# SCH_Cocktail-Hat-Solder-Terminals_2026-0.net
KiCad netlist of a schematic drawn in EasyEDA
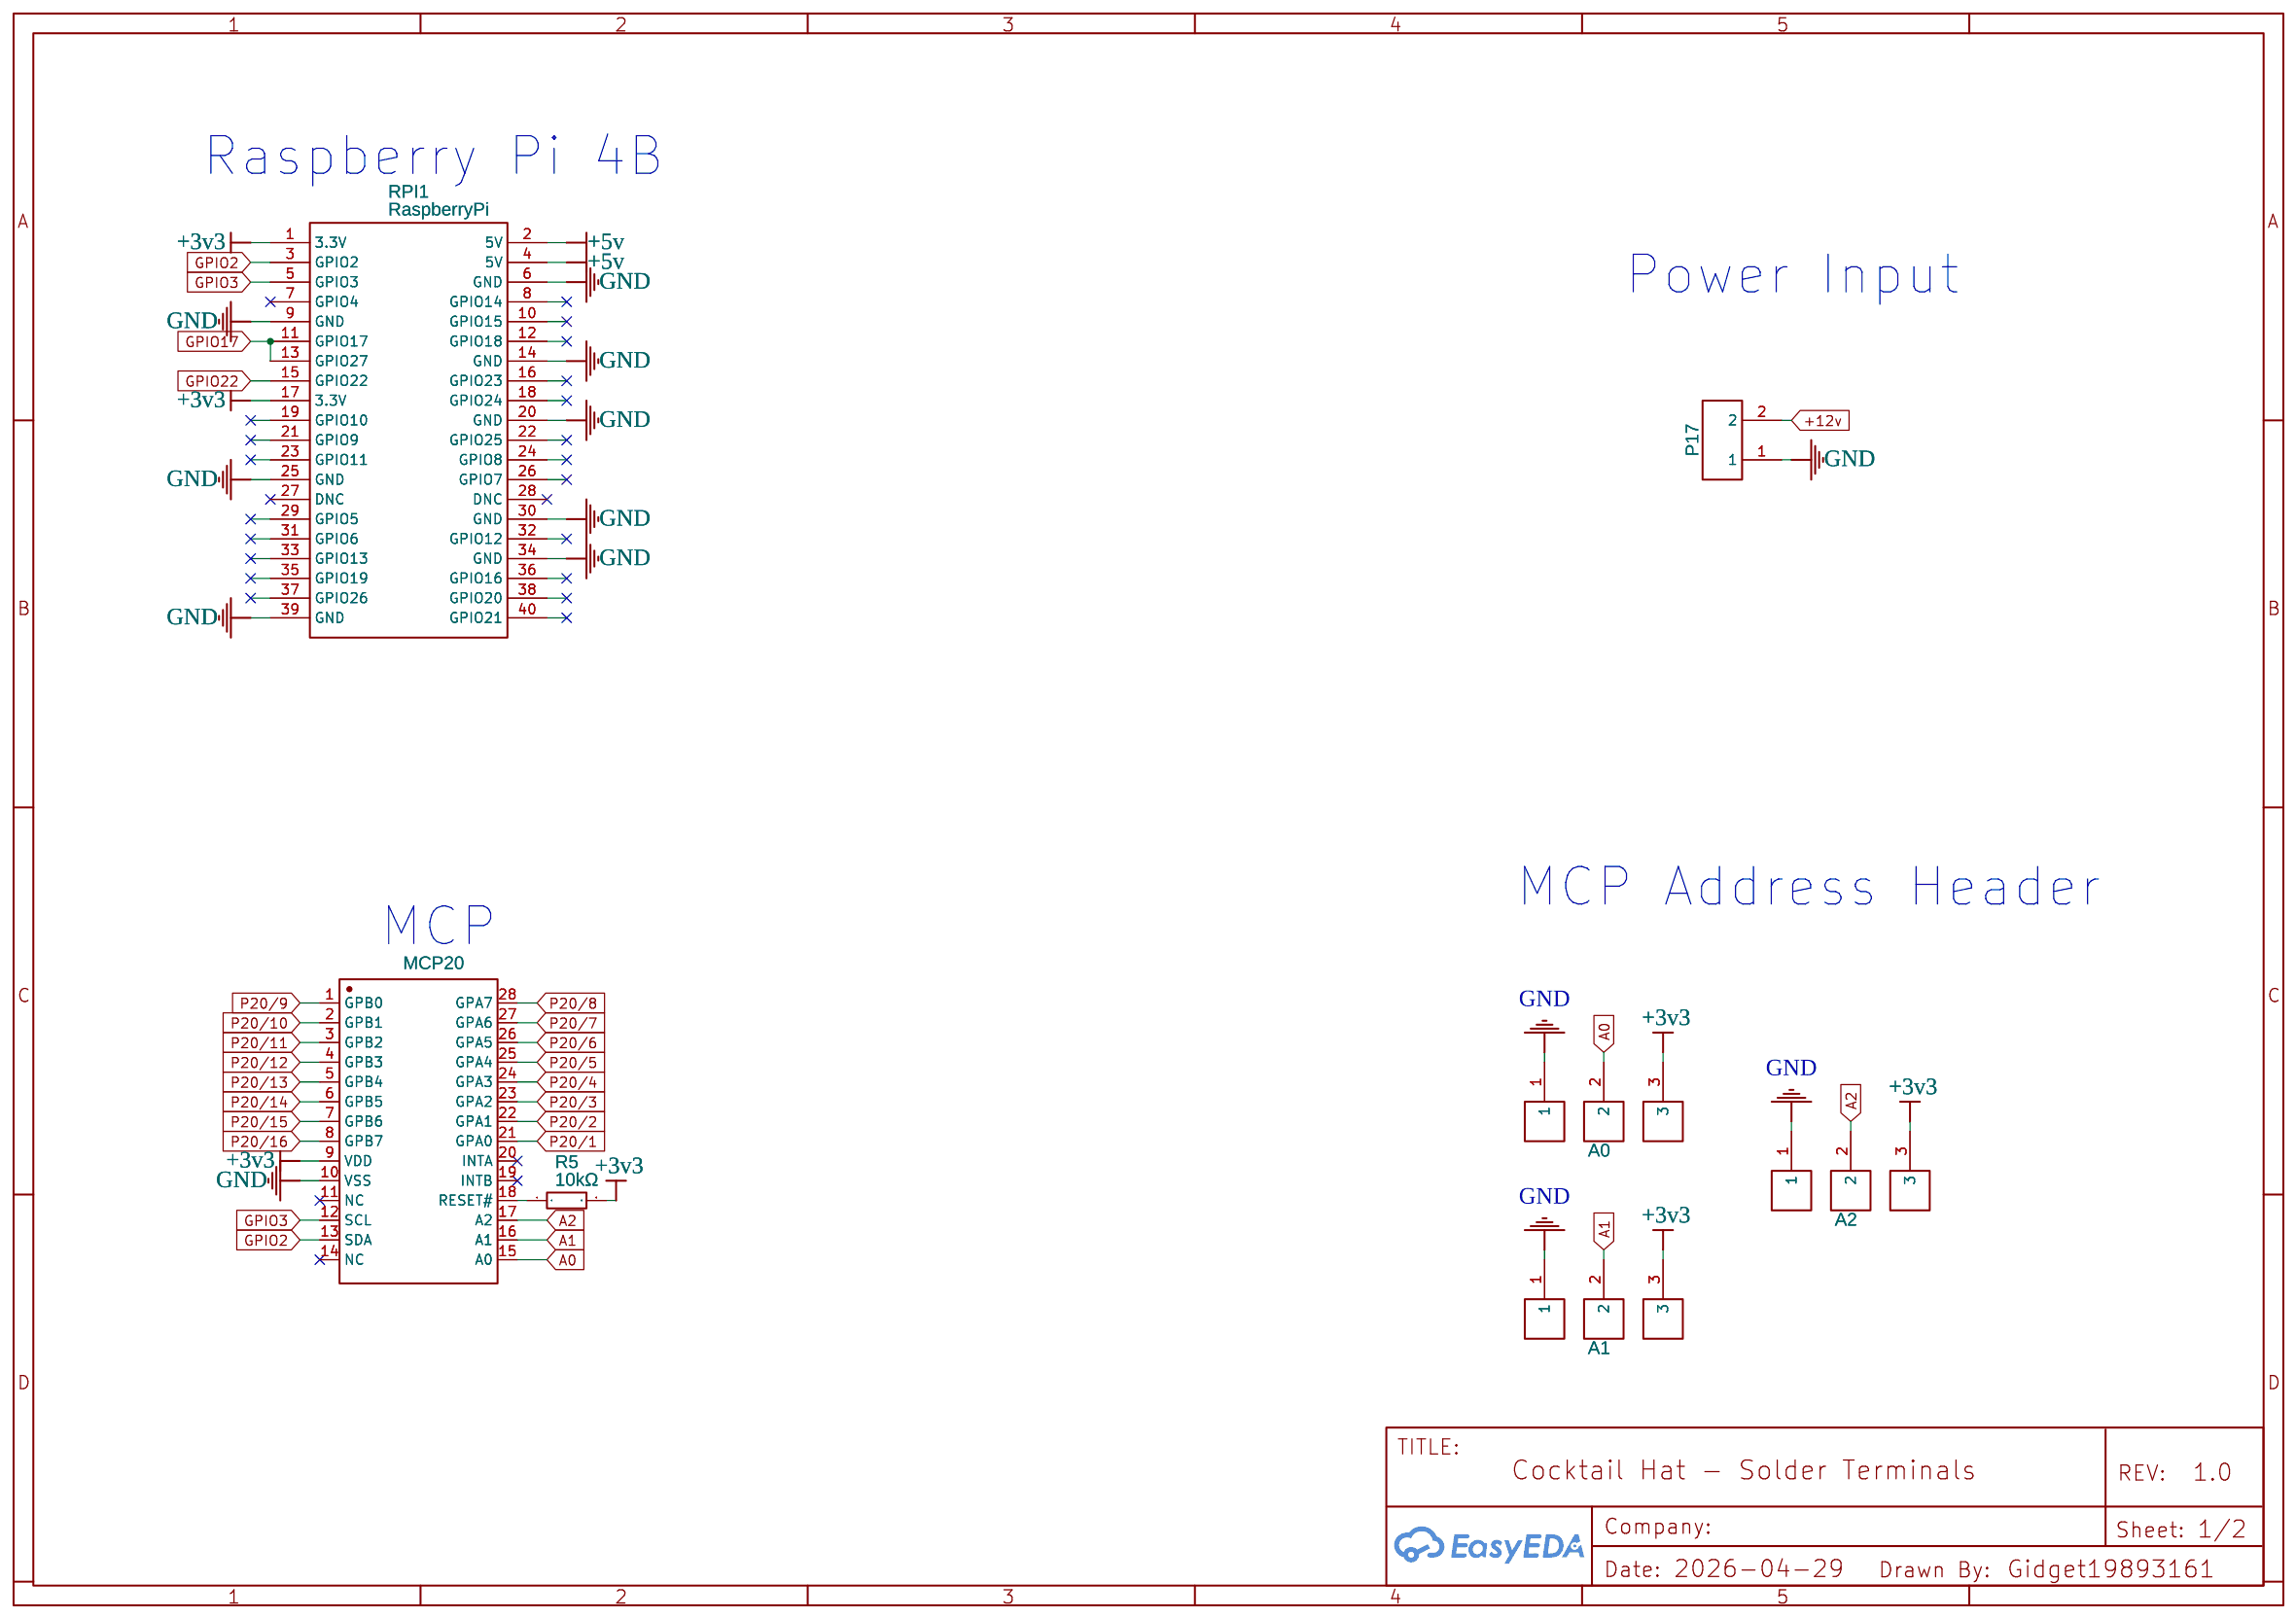
[diagram p0: Main]
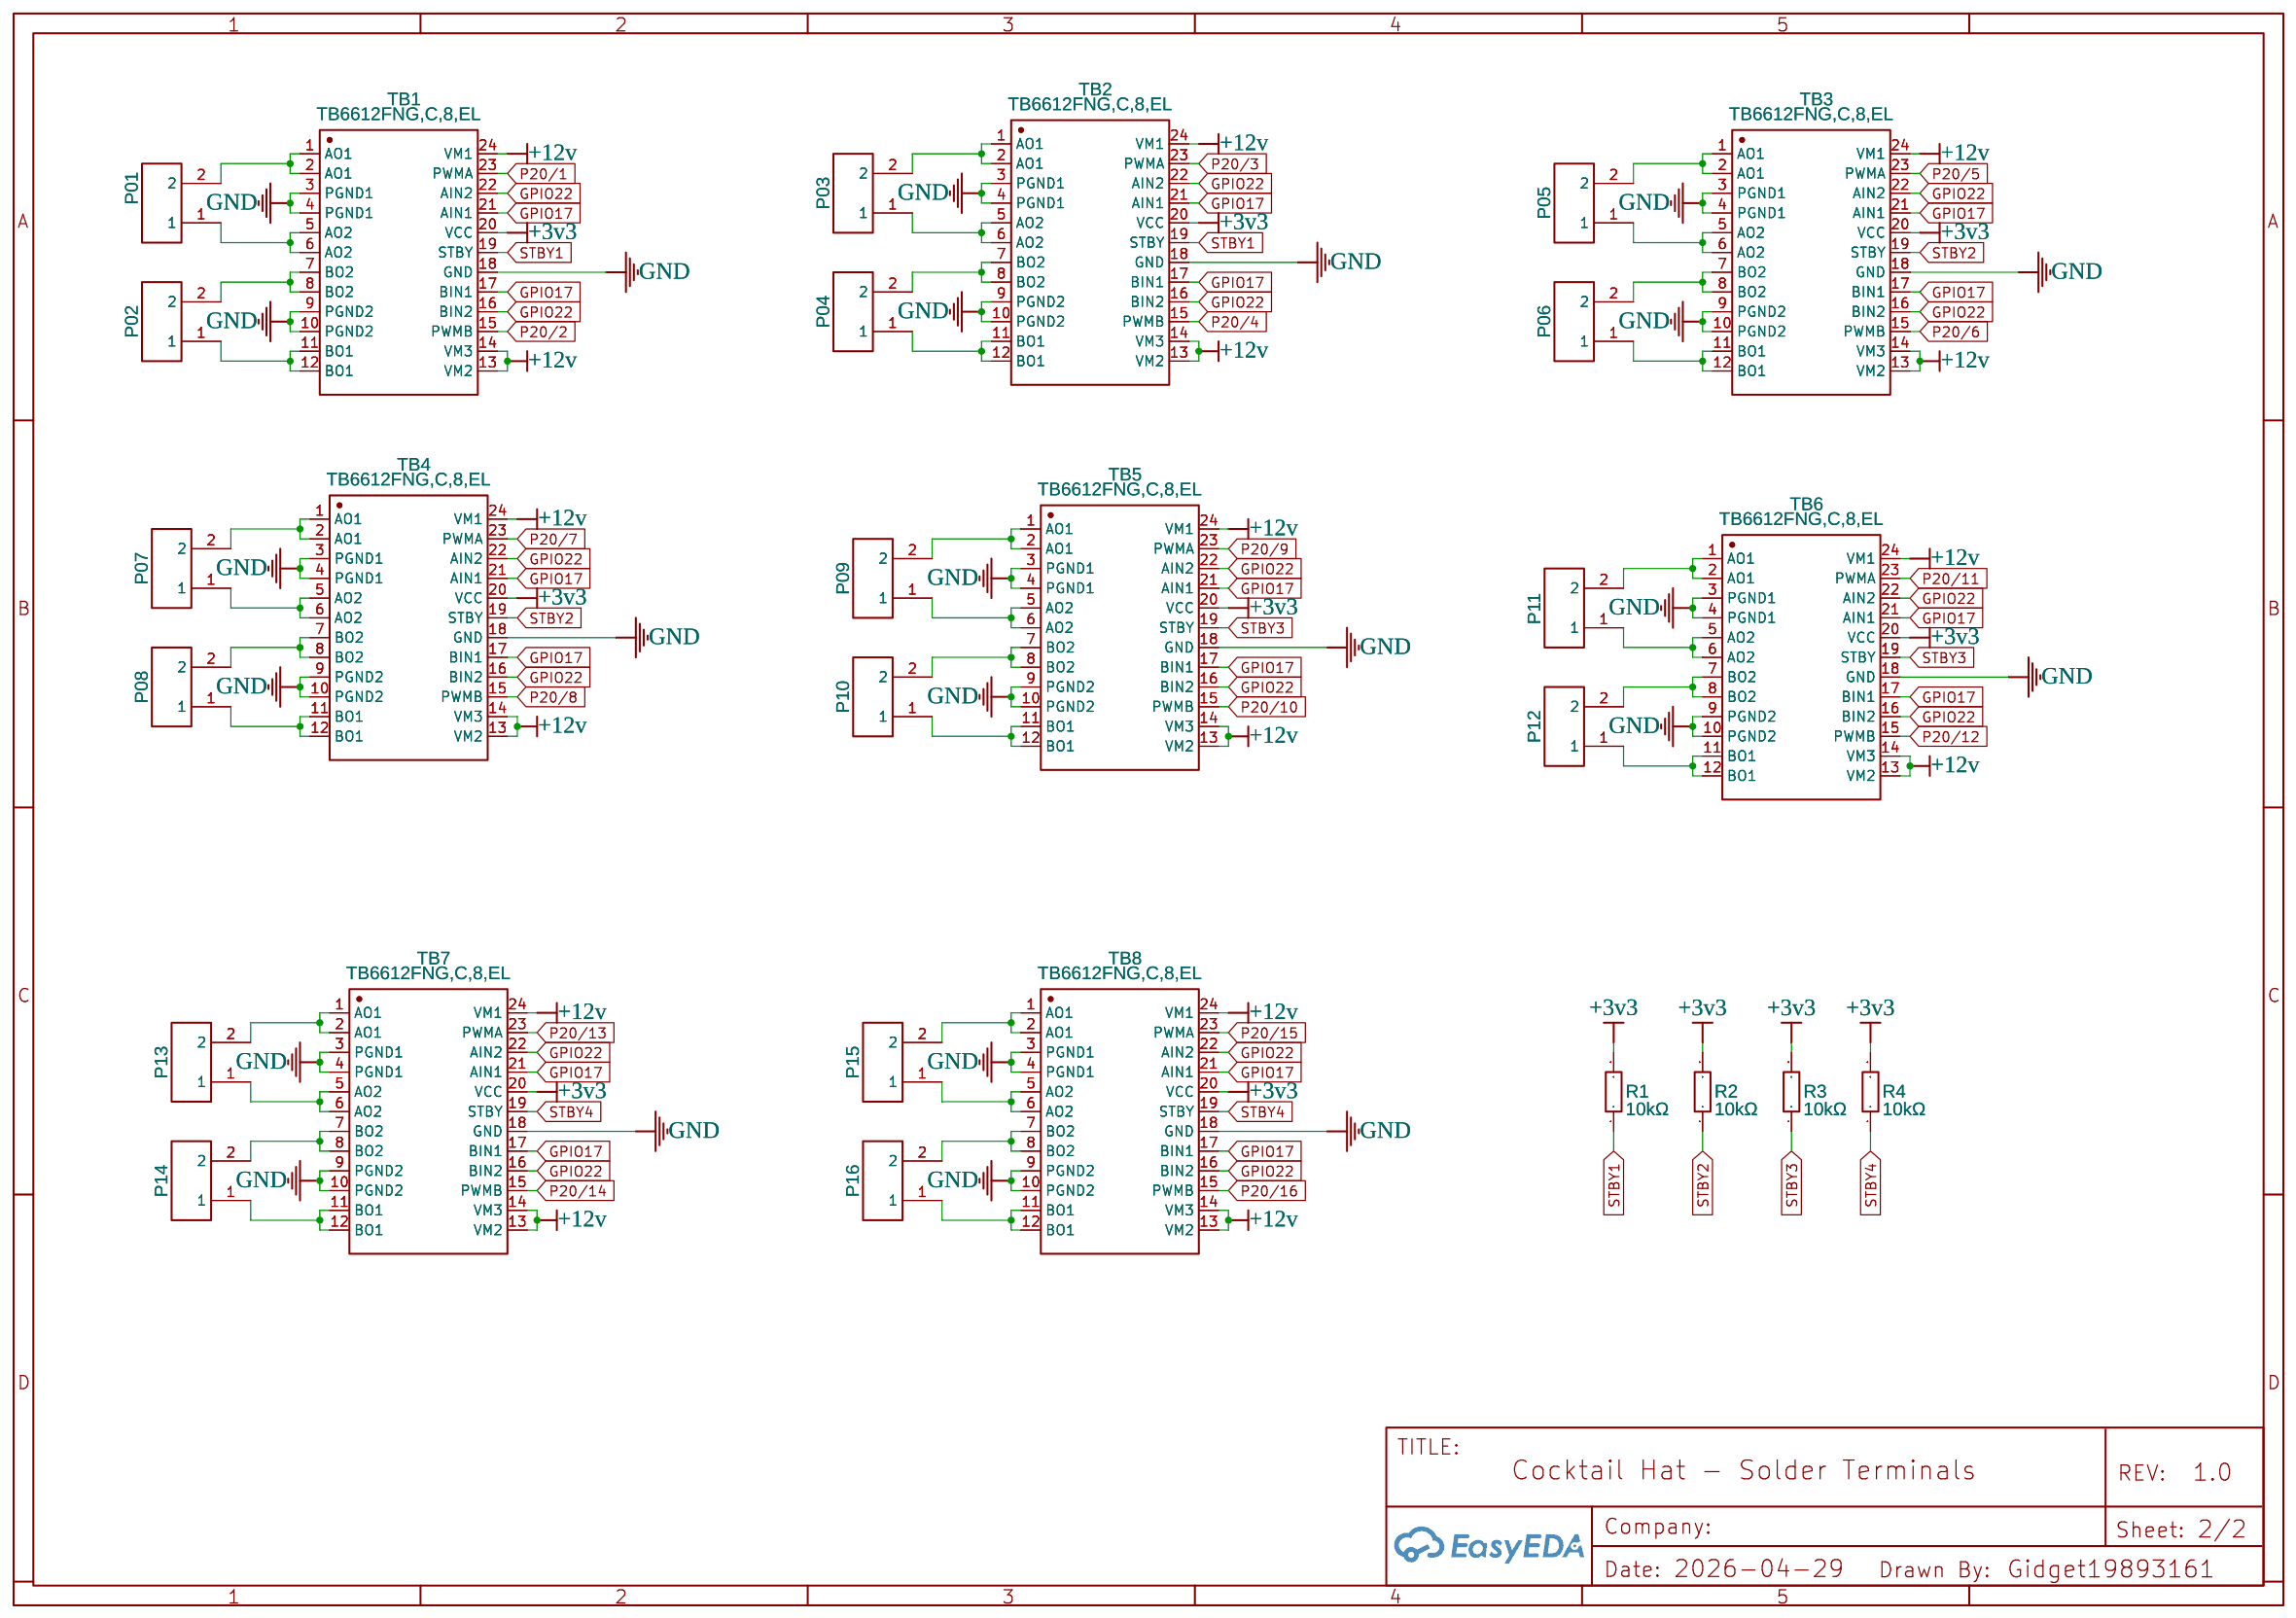
[diagram p1: TB20]

(export (version "E")
  (design (tool "Eeschema 10.0.6"))
  (components
    (comp (ref "A0") (value "JUMPER_3_PADS") (libsource (lib "") (part "JUMPER_3_PADS")))
    (comp (ref "A1") (value "JUMPER_3_PADS") (libsource (lib "") (part "JUMPER_3_PADS")))
    (comp (ref "A2") (value "JUMPER_3_PADS") (libsource (lib "") (part "JUMPER_3_PADS")))
    (comp (ref "MCP20")
      (value "MCP23017-E/SO")
      (fields (field (name "Manufacturer") "MICROCHIP(美国微芯)"))
      (libsource (lib "") (part "MCP23017-E/SO"))
    )
    (comp (ref "P17") (value "PAD") (libsource (lib "") (part "PAD")))
    (comp (ref "R5")
      (value "10kΩ")
      (fields
        (field (name "Manufacturer Part") "1206W4F1002T5E")
        (field (name "Manufacturer") "UNI-ROYAL(厚声)")
      )
      (libsource (lib "") (part "1206W4F1002T5E"))
    )
    (comp (ref "RPI1") (value "RaspberryPi") (libsource (lib "") (part "RaspberryPi")))
    (comp (ref "P01") (value "PAD") (libsource (lib "") (part "PAD")))
    (comp (ref "P02") (value "PAD") (libsource (lib "") (part "PAD")))
    (comp (ref "P03") (value "PAD") (libsource (lib "") (part "PAD")))
    (comp (ref "P04") (value "PAD") (libsource (lib "") (part "PAD")))
    (comp (ref "P05") (value "PAD") (libsource (lib "") (part "PAD")))
    (comp (ref "P06") (value "PAD") (libsource (lib "") (part "PAD")))
    (comp (ref "P07") (value "PAD") (libsource (lib "") (part "PAD")))
    (comp (ref "P08") (value "PAD") (libsource (lib "") (part "PAD")))
    (comp (ref "P09") (value "PAD") (libsource (lib "") (part "PAD")))
    (comp (ref "P10") (value "PAD") (libsource (lib "") (part "PAD")))
    (comp (ref "P11") (value "PAD") (libsource (lib "") (part "PAD")))
    (comp (ref "P12") (value "PAD") (libsource (lib "") (part "PAD")))
    (comp (ref "P13") (value "PAD") (libsource (lib "") (part "PAD")))
    (comp (ref "P14") (value "PAD") (libsource (lib "") (part "PAD")))
    (comp (ref "P15") (value "PAD") (libsource (lib "") (part "PAD")))
    (comp (ref "P16") (value "PAD") (libsource (lib "") (part "PAD")))
    (comp (ref "R1")
      (value "10kΩ")
      (fields
        (field (name "Manufacturer Part") "1206W4F1002T5E")
        (field (name "Manufacturer") "UNI-ROYAL(厚声)")
      )
      (libsource (lib "") (part "1206W4F1002T5E"))
    )
    (comp (ref "R2")
      (value "10kΩ")
      (fields
        (field (name "Manufacturer Part") "1206W4F1002T5E")
        (field (name "Manufacturer") "UNI-ROYAL(厚声)")
      )
      (libsource (lib "") (part "1206W4F1002T5E"))
    )
    (comp (ref "R3")
      (value "10kΩ")
      (fields
        (field (name "Manufacturer Part") "1206W4F1002T5E")
        (field (name "Manufacturer") "UNI-ROYAL(厚声)")
      )
      (libsource (lib "") (part "1206W4F1002T5E"))
    )
    (comp (ref "R4")
      (value "10kΩ")
      (fields
        (field (name "Manufacturer Part") "1206W4F1002T5E")
        (field (name "Manufacturer") "UNI-ROYAL(厚声)")
      )
      (libsource (lib "") (part "1206W4F1002T5E"))
    )
    (comp (ref "TB1")
      (value "TB6612FNG,C,8,EL")
      (fields (field (name "Manufacturer") "TOSHIBA(东芝)"))
      (libsource (lib "") (part "TB6612FNG,C,8,EL"))
    )
    (comp (ref "TB2")
      (value "TB6612FNG,C,8,EL")
      (fields (field (name "Manufacturer") "TOSHIBA(东芝)"))
      (libsource (lib "") (part "TB6612FNG,C,8,EL"))
    )
    (comp (ref "TB3")
      (value "TB6612FNG,C,8,EL")
      (fields (field (name "Manufacturer") "TOSHIBA(东芝)"))
      (libsource (lib "") (part "TB6612FNG,C,8,EL"))
    )
    (comp (ref "TB4")
      (value "TB6612FNG,C,8,EL")
      (fields (field (name "Manufacturer") "TOSHIBA(东芝)"))
      (libsource (lib "") (part "TB6612FNG,C,8,EL"))
    )
    (comp (ref "TB5")
      (value "TB6612FNG,C,8,EL")
      (fields (field (name "Manufacturer") "TOSHIBA(东芝)"))
      (libsource (lib "") (part "TB6612FNG,C,8,EL"))
    )
    (comp (ref "TB6")
      (value "TB6612FNG,C,8,EL")
      (fields (field (name "Manufacturer") "TOSHIBA(东芝)"))
      (libsource (lib "") (part "TB6612FNG,C,8,EL"))
    )
    (comp (ref "TB7")
      (value "TB6612FNG,C,8,EL")
      (fields (field (name "Manufacturer") "TOSHIBA(东芝)"))
      (libsource (lib "") (part "TB6612FNG,C,8,EL"))
    )
    (comp (ref "TB8")
      (value "TB6612FNG,C,8,EL")
      (fields (field (name "Manufacturer") "TOSHIBA(东芝)"))
      (libsource (lib "") (part "TB6612FNG,C,8,EL"))
    )
  )
  (nets
    (net (code "1") (name "+3v3") (class "Default")
      (node (ref "A0") (pin "3") (pinfunction "3_3") (pintype "unspecified"))
      (node (ref "A1") (pin "3") (pinfunction "3_3") (pintype "unspecified"))
      (node (ref "A2") (pin "3") (pinfunction "3_3") (pintype "unspecified"))
      (node (ref "MCP20") (pin "9") (pinfunction "VDD_9") (pintype "unspecified"))
      (node (ref "R1") (pin "2") (pinfunction "2_2") (pintype "input"))
      (node (ref "R2") (pin "2") (pinfunction "2_2") (pintype "input"))
      (node (ref "R3") (pin "2") (pinfunction "2_2") (pintype "input"))
      (node (ref "R4") (pin "2") (pinfunction "2_2") (pintype "input"))
      (node (ref "R5") (pin "2") (pinfunction "2_2") (pintype "input"))
      (node (ref "RPI1") (pin "1") (pinfunction "3.3V_1") (pintype "unspecified"))
      (node (ref "RPI1") (pin "17") (pinfunction "3.3V_17") (pintype "unspecified"))
      (node (ref "TB1") (pin "20") (pinfunction "VCC_20") (pintype "unspecified"))
      (node (ref "TB2") (pin "20") (pinfunction "VCC_20") (pintype "unspecified"))
      (node (ref "TB3") (pin "20") (pinfunction "VCC_20") (pintype "unspecified"))
      (node (ref "TB4") (pin "20") (pinfunction "VCC_20") (pintype "unspecified"))
      (node (ref "TB5") (pin "20") (pinfunction "VCC_20") (pintype "unspecified"))
      (node (ref "TB6") (pin "20") (pinfunction "VCC_20") (pintype "unspecified"))
      (node (ref "TB7") (pin "20") (pinfunction "VCC_20") (pintype "unspecified"))
      (node (ref "TB8") (pin "20") (pinfunction "VCC_20") (pintype "unspecified"))
    )
    (net (code "2") (name "+5v") (class "Default")
      (node (ref "RPI1") (pin "2") (pinfunction "5V_2") (pintype "unspecified"))
      (node (ref "RPI1") (pin "4") (pinfunction "5V_4") (pintype "unspecified"))
    )
    (net (code "3") (name "+12v") (class "Default")
      (node (ref "P17") (pin "2") (pinfunction "2_2") (pintype "unspecified"))
      (node (ref "TB1") (pin "13") (pinfunction "VM2_13") (pintype "unspecified"))
      (node (ref "TB1") (pin "14") (pinfunction "VM3_14") (pintype "unspecified"))
      (node (ref "TB1") (pin "24") (pinfunction "VM1_24") (pintype "unspecified"))
      (node (ref "TB2") (pin "13") (pinfunction "VM2_13") (pintype "unspecified"))
      (node (ref "TB2") (pin "14") (pinfunction "VM3_14") (pintype "unspecified"))
      (node (ref "TB2") (pin "24") (pinfunction "VM1_24") (pintype "unspecified"))
      (node (ref "TB3") (pin "13") (pinfunction "VM2_13") (pintype "unspecified"))
      (node (ref "TB3") (pin "14") (pinfunction "VM3_14") (pintype "unspecified"))
      (node (ref "TB3") (pin "24") (pinfunction "VM1_24") (pintype "unspecified"))
      (node (ref "TB4") (pin "13") (pinfunction "VM2_13") (pintype "unspecified"))
      (node (ref "TB4") (pin "14") (pinfunction "VM3_14") (pintype "unspecified"))
      (node (ref "TB4") (pin "24") (pinfunction "VM1_24") (pintype "unspecified"))
      (node (ref "TB5") (pin "13") (pinfunction "VM2_13") (pintype "unspecified"))
      (node (ref "TB5") (pin "14") (pinfunction "VM3_14") (pintype "unspecified"))
      (node (ref "TB5") (pin "24") (pinfunction "VM1_24") (pintype "unspecified"))
      (node (ref "TB6") (pin "13") (pinfunction "VM2_13") (pintype "unspecified"))
      (node (ref "TB6") (pin "14") (pinfunction "VM3_14") (pintype "unspecified"))
      (node (ref "TB6") (pin "24") (pinfunction "VM1_24") (pintype "unspecified"))
      (node (ref "TB7") (pin "13") (pinfunction "VM2_13") (pintype "unspecified"))
      (node (ref "TB7") (pin "14") (pinfunction "VM3_14") (pintype "unspecified"))
      (node (ref "TB7") (pin "24") (pinfunction "VM1_24") (pintype "unspecified"))
      (node (ref "TB8") (pin "13") (pinfunction "VM2_13") (pintype "unspecified"))
      (node (ref "TB8") (pin "14") (pinfunction "VM3_14") (pintype "unspecified"))
      (node (ref "TB8") (pin "24") (pinfunction "VM1_24") (pintype "unspecified"))
    )
    (net (code "4") (name "A0") (class "Default")
      (node (ref "A0") (pin "2") (pinfunction "2_2") (pintype "unspecified"))
      (node (ref "MCP20") (pin "15") (pinfunction "A0_15") (pintype "unspecified"))
    )
    (net (code "5") (name "A1") (class "Default")
      (node (ref "A1") (pin "2") (pinfunction "2_2") (pintype "unspecified"))
      (node (ref "MCP20") (pin "16") (pinfunction "A1_16") (pintype "unspecified"))
    )
    (net (code "6") (name "A2") (class "Default")
      (node (ref "A2") (pin "2") (pinfunction "2_2") (pintype "unspecified"))
      (node (ref "MCP20") (pin "17") (pinfunction "A2_17") (pintype "unspecified"))
    )
    (net (code "7") (name "GND") (class "Default")
      (node (ref "A0") (pin "1") (pinfunction "1_1") (pintype "unspecified"))
      (node (ref "A1") (pin "1") (pinfunction "1_1") (pintype "unspecified"))
      (node (ref "A2") (pin "1") (pinfunction "1_1") (pintype "unspecified"))
      (node (ref "MCP20") (pin "10") (pinfunction "VSS_10") (pintype "unspecified"))
      (node (ref "P17") (pin "1") (pinfunction "1_1") (pintype "unspecified"))
      (node (ref "RPI1") (pin "14") (pinfunction "GND_14") (pintype "unspecified"))
      (node (ref "RPI1") (pin "20") (pinfunction "GND_20") (pintype "unspecified"))
      (node (ref "RPI1") (pin "25") (pinfunction "GND_25") (pintype "unspecified"))
      (node (ref "RPI1") (pin "30") (pinfunction "GND_30") (pintype "unspecified"))
      (node (ref "RPI1") (pin "34") (pinfunction "GND_34") (pintype "unspecified"))
      (node (ref "RPI1") (pin "39") (pinfunction "GND_39") (pintype "unspecified"))
      (node (ref "RPI1") (pin "6") (pinfunction "GND_6") (pintype "unspecified"))
      (node (ref "RPI1") (pin "9") (pinfunction "GND_9") (pintype "unspecified"))
      (node (ref "TB1") (pin "10") (pinfunction "PGND2_10") (pintype "unspecified"))
      (node (ref "TB1") (pin "18") (pinfunction "GND_18") (pintype "unspecified"))
      (node (ref "TB1") (pin "3") (pinfunction "PGND1_3") (pintype "unspecified"))
      (node (ref "TB1") (pin "4") (pinfunction "PGND1_4") (pintype "unspecified"))
      (node (ref "TB1") (pin "9") (pinfunction "PGND2_9") (pintype "unspecified"))
      (node (ref "TB2") (pin "10") (pinfunction "PGND2_10") (pintype "unspecified"))
      (node (ref "TB2") (pin "18") (pinfunction "GND_18") (pintype "unspecified"))
      (node (ref "TB2") (pin "3") (pinfunction "PGND1_3") (pintype "unspecified"))
      (node (ref "TB2") (pin "4") (pinfunction "PGND1_4") (pintype "unspecified"))
      (node (ref "TB2") (pin "9") (pinfunction "PGND2_9") (pintype "unspecified"))
      (node (ref "TB3") (pin "10") (pinfunction "PGND2_10") (pintype "unspecified"))
      (node (ref "TB3") (pin "18") (pinfunction "GND_18") (pintype "unspecified"))
      (node (ref "TB3") (pin "3") (pinfunction "PGND1_3") (pintype "unspecified"))
      (node (ref "TB3") (pin "4") (pinfunction "PGND1_4") (pintype "unspecified"))
      (node (ref "TB3") (pin "9") (pinfunction "PGND2_9") (pintype "unspecified"))
      (node (ref "TB4") (pin "10") (pinfunction "PGND2_10") (pintype "unspecified"))
      (node (ref "TB4") (pin "18") (pinfunction "GND_18") (pintype "unspecified"))
      (node (ref "TB4") (pin "3") (pinfunction "PGND1_3") (pintype "unspecified"))
      (node (ref "TB4") (pin "4") (pinfunction "PGND1_4") (pintype "unspecified"))
      (node (ref "TB4") (pin "9") (pinfunction "PGND2_9") (pintype "unspecified"))
      (node (ref "TB5") (pin "10") (pinfunction "PGND2_10") (pintype "unspecified"))
      (node (ref "TB5") (pin "18") (pinfunction "GND_18") (pintype "unspecified"))
      (node (ref "TB5") (pin "3") (pinfunction "PGND1_3") (pintype "unspecified"))
      (node (ref "TB5") (pin "4") (pinfunction "PGND1_4") (pintype "unspecified"))
      (node (ref "TB5") (pin "9") (pinfunction "PGND2_9") (pintype "unspecified"))
      (node (ref "TB6") (pin "10") (pinfunction "PGND2_10") (pintype "unspecified"))
      (node (ref "TB6") (pin "18") (pinfunction "GND_18") (pintype "unspecified"))
      (node (ref "TB6") (pin "3") (pinfunction "PGND1_3") (pintype "unspecified"))
      (node (ref "TB6") (pin "4") (pinfunction "PGND1_4") (pintype "unspecified"))
      (node (ref "TB6") (pin "9") (pinfunction "PGND2_9") (pintype "unspecified"))
      (node (ref "TB7") (pin "10") (pinfunction "PGND2_10") (pintype "unspecified"))
      (node (ref "TB7") (pin "18") (pinfunction "GND_18") (pintype "unspecified"))
      (node (ref "TB7") (pin "3") (pinfunction "PGND1_3") (pintype "unspecified"))
      (node (ref "TB7") (pin "4") (pinfunction "PGND1_4") (pintype "unspecified"))
      (node (ref "TB7") (pin "9") (pinfunction "PGND2_9") (pintype "unspecified"))
      (node (ref "TB8") (pin "10") (pinfunction "PGND2_10") (pintype "unspecified"))
      (node (ref "TB8") (pin "18") (pinfunction "GND_18") (pintype "unspecified"))
      (node (ref "TB8") (pin "3") (pinfunction "PGND1_3") (pintype "unspecified"))
      (node (ref "TB8") (pin "4") (pinfunction "PGND1_4") (pintype "unspecified"))
      (node (ref "TB8") (pin "9") (pinfunction "PGND2_9") (pintype "unspecified"))
    )
    (net (code "8") (name "GPIO2") (class "Default")
      (node (ref "MCP20") (pin "13") (pinfunction "SDA_13") (pintype "unspecified"))
      (node (ref "RPI1") (pin "3") (pinfunction "GPIO2_3") (pintype "unspecified"))
    )
    (net (code "9") (name "GPIO3") (class "Default")
      (node (ref "MCP20") (pin "12") (pinfunction "SCL_12") (pintype "unspecified"))
      (node (ref "RPI1") (pin "5") (pinfunction "GPIO3_5") (pintype "unspecified"))
    )
    (net (code "10") (name "GPIO17") (class "Default")
      (node (ref "RPI1") (pin "11") (pinfunction "GPIO17_11") (pintype "unspecified"))
      (node (ref "RPI1") (pin "13") (pinfunction "GPIO27_13") (pintype "unspecified"))
      (node (ref "TB1") (pin "17") (pinfunction "BIN1_17") (pintype "unspecified"))
      (node (ref "TB1") (pin "21") (pinfunction "AIN1_21") (pintype "unspecified"))
      (node (ref "TB2") (pin "17") (pinfunction "BIN1_17") (pintype "unspecified"))
      (node (ref "TB2") (pin "21") (pinfunction "AIN1_21") (pintype "unspecified"))
      (node (ref "TB3") (pin "17") (pinfunction "BIN1_17") (pintype "unspecified"))
      (node (ref "TB3") (pin "21") (pinfunction "AIN1_21") (pintype "unspecified"))
      (node (ref "TB4") (pin "17") (pinfunction "BIN1_17") (pintype "unspecified"))
      (node (ref "TB4") (pin "21") (pinfunction "AIN1_21") (pintype "unspecified"))
      (node (ref "TB5") (pin "17") (pinfunction "BIN1_17") (pintype "unspecified"))
      (node (ref "TB5") (pin "21") (pinfunction "AIN1_21") (pintype "unspecified"))
      (node (ref "TB6") (pin "17") (pinfunction "BIN1_17") (pintype "unspecified"))
      (node (ref "TB6") (pin "21") (pinfunction "AIN1_21") (pintype "unspecified"))
      (node (ref "TB7") (pin "17") (pinfunction "BIN1_17") (pintype "unspecified"))
      (node (ref "TB7") (pin "21") (pinfunction "AIN1_21") (pintype "unspecified"))
      (node (ref "TB8") (pin "17") (pinfunction "BIN1_17") (pintype "unspecified"))
      (node (ref "TB8") (pin "21") (pinfunction "AIN1_21") (pintype "unspecified"))
    )
    (net (code "11") (name "GPIO22") (class "Default")
      (node (ref "RPI1") (pin "15") (pinfunction "GPIO22_15") (pintype "unspecified"))
      (node (ref "TB1") (pin "16") (pinfunction "BIN2_16") (pintype "unspecified"))
      (node (ref "TB1") (pin "22") (pinfunction "AIN2_22") (pintype "unspecified"))
      (node (ref "TB2") (pin "16") (pinfunction "BIN2_16") (pintype "unspecified"))
      (node (ref "TB2") (pin "22") (pinfunction "AIN2_22") (pintype "unspecified"))
      (node (ref "TB3") (pin "16") (pinfunction "BIN2_16") (pintype "unspecified"))
      (node (ref "TB3") (pin "22") (pinfunction "AIN2_22") (pintype "unspecified"))
      (node (ref "TB4") (pin "16") (pinfunction "BIN2_16") (pintype "unspecified"))
      (node (ref "TB4") (pin "22") (pinfunction "AIN2_22") (pintype "unspecified"))
      (node (ref "TB5") (pin "16") (pinfunction "BIN2_16") (pintype "unspecified"))
      (node (ref "TB5") (pin "22") (pinfunction "AIN2_22") (pintype "unspecified"))
      (node (ref "TB6") (pin "16") (pinfunction "BIN2_16") (pintype "unspecified"))
      (node (ref "TB6") (pin "22") (pinfunction "AIN2_22") (pintype "unspecified"))
      (node (ref "TB7") (pin "16") (pinfunction "BIN2_16") (pintype "unspecified"))
      (node (ref "TB7") (pin "22") (pinfunction "AIN2_22") (pintype "unspecified"))
      (node (ref "TB8") (pin "16") (pinfunction "BIN2_16") (pintype "unspecified"))
      (node (ref "TB8") (pin "22") (pinfunction "AIN2_22") (pintype "unspecified"))
    )
    (net (code "12") (name "Net-(MCP20-RESET#)") (class "Default")
      (node (ref "MCP20") (pin "18") (pinfunction "RESET#_18") (pintype "unspecified"))
      (node (ref "R5") (pin "1") (pinfunction "1_1") (pintype "input"))
    )
    (net (code "13") (name "Net-(P01-Pad1)") (class "Default")
      (node (ref "P01") (pin "1") (pinfunction "1_1") (pintype "unspecified"))
      (node (ref "TB1") (pin "5") (pinfunction "AO2_5") (pintype "unspecified"))
      (node (ref "TB1") (pin "6") (pinfunction "AO2_6") (pintype "unspecified"))
    )
    (net (code "14") (name "Net-(P01-Pad2)") (class "Default")
      (node (ref "P01") (pin "2") (pinfunction "2_2") (pintype "unspecified"))
      (node (ref "TB1") (pin "1") (pinfunction "AO1_1") (pintype "unspecified"))
      (node (ref "TB1") (pin "2") (pinfunction "AO1_2") (pintype "unspecified"))
    )
    (net (code "15") (name "Net-(P02-Pad1)") (class "Default")
      (node (ref "P02") (pin "1") (pinfunction "1_1") (pintype "unspecified"))
      (node (ref "TB1") (pin "11") (pinfunction "BO1_11") (pintype "unspecified"))
      (node (ref "TB1") (pin "12") (pinfunction "BO1_12") (pintype "unspecified"))
    )
    (net (code "16") (name "Net-(P02-Pad2)") (class "Default")
      (node (ref "P02") (pin "2") (pinfunction "2_2") (pintype "unspecified"))
      (node (ref "TB1") (pin "7") (pinfunction "BO2_7") (pintype "unspecified"))
      (node (ref "TB1") (pin "8") (pinfunction "BO2_8") (pintype "unspecified"))
    )
    (net (code "17") (name "Net-(P03-Pad1)") (class "Default")
      (node (ref "P03") (pin "1") (pinfunction "1_1") (pintype "unspecified"))
      (node (ref "TB2") (pin "5") (pinfunction "AO2_5") (pintype "unspecified"))
      (node (ref "TB2") (pin "6") (pinfunction "AO2_6") (pintype "unspecified"))
    )
    (net (code "18") (name "Net-(P03-Pad2)") (class "Default")
      (node (ref "P03") (pin "2") (pinfunction "2_2") (pintype "unspecified"))
      (node (ref "TB2") (pin "1") (pinfunction "AO1_1") (pintype "unspecified"))
      (node (ref "TB2") (pin "2") (pinfunction "AO1_2") (pintype "unspecified"))
    )
    (net (code "19") (name "Net-(P04-Pad1)") (class "Default")
      (node (ref "P04") (pin "1") (pinfunction "1_1") (pintype "unspecified"))
      (node (ref "TB2") (pin "11") (pinfunction "BO1_11") (pintype "unspecified"))
      (node (ref "TB2") (pin "12") (pinfunction "BO1_12") (pintype "unspecified"))
    )
    (net (code "20") (name "Net-(P04-Pad2)") (class "Default")
      (node (ref "P04") (pin "2") (pinfunction "2_2") (pintype "unspecified"))
      (node (ref "TB2") (pin "7") (pinfunction "BO2_7") (pintype "unspecified"))
      (node (ref "TB2") (pin "8") (pinfunction "BO2_8") (pintype "unspecified"))
    )
    (net (code "21") (name "Net-(P05-Pad1)") (class "Default")
      (node (ref "P05") (pin "1") (pinfunction "1_1") (pintype "unspecified"))
      (node (ref "TB3") (pin "5") (pinfunction "AO2_5") (pintype "unspecified"))
      (node (ref "TB3") (pin "6") (pinfunction "AO2_6") (pintype "unspecified"))
    )
    (net (code "22") (name "Net-(P05-Pad2)") (class "Default")
      (node (ref "P05") (pin "2") (pinfunction "2_2") (pintype "unspecified"))
      (node (ref "TB3") (pin "1") (pinfunction "AO1_1") (pintype "unspecified"))
      (node (ref "TB3") (pin "2") (pinfunction "AO1_2") (pintype "unspecified"))
    )
    (net (code "23") (name "Net-(P06-Pad1)") (class "Default")
      (node (ref "P06") (pin "1") (pinfunction "1_1") (pintype "unspecified"))
      (node (ref "TB3") (pin "11") (pinfunction "BO1_11") (pintype "unspecified"))
      (node (ref "TB3") (pin "12") (pinfunction "BO1_12") (pintype "unspecified"))
    )
    (net (code "24") (name "Net-(P06-Pad2)") (class "Default")
      (node (ref "P06") (pin "2") (pinfunction "2_2") (pintype "unspecified"))
      (node (ref "TB3") (pin "7") (pinfunction "BO2_7") (pintype "unspecified"))
      (node (ref "TB3") (pin "8") (pinfunction "BO2_8") (pintype "unspecified"))
    )
    (net (code "25") (name "Net-(P07-Pad1)") (class "Default")
      (node (ref "P07") (pin "1") (pinfunction "1_1") (pintype "unspecified"))
      (node (ref "TB4") (pin "5") (pinfunction "AO2_5") (pintype "unspecified"))
      (node (ref "TB4") (pin "6") (pinfunction "AO2_6") (pintype "unspecified"))
    )
    (net (code "26") (name "Net-(P07-Pad2)") (class "Default")
      (node (ref "P07") (pin "2") (pinfunction "2_2") (pintype "unspecified"))
      (node (ref "TB4") (pin "1") (pinfunction "AO1_1") (pintype "unspecified"))
      (node (ref "TB4") (pin "2") (pinfunction "AO1_2") (pintype "unspecified"))
    )
    (net (code "27") (name "Net-(P08-Pad1)") (class "Default")
      (node (ref "P08") (pin "1") (pinfunction "1_1") (pintype "unspecified"))
      (node (ref "TB4") (pin "11") (pinfunction "BO1_11") (pintype "unspecified"))
      (node (ref "TB4") (pin "12") (pinfunction "BO1_12") (pintype "unspecified"))
    )
    (net (code "28") (name "Net-(P08-Pad2)") (class "Default")
      (node (ref "P08") (pin "2") (pinfunction "2_2") (pintype "unspecified"))
      (node (ref "TB4") (pin "7") (pinfunction "BO2_7") (pintype "unspecified"))
      (node (ref "TB4") (pin "8") (pinfunction "BO2_8") (pintype "unspecified"))
    )
    (net (code "29") (name "Net-(P09-Pad1)") (class "Default")
      (node (ref "P09") (pin "1") (pinfunction "1_1") (pintype "unspecified"))
      (node (ref "TB5") (pin "5") (pinfunction "AO2_5") (pintype "unspecified"))
      (node (ref "TB5") (pin "6") (pinfunction "AO2_6") (pintype "unspecified"))
    )
    (net (code "30") (name "Net-(P09-Pad2)") (class "Default")
      (node (ref "P09") (pin "2") (pinfunction "2_2") (pintype "unspecified"))
      (node (ref "TB5") (pin "1") (pinfunction "AO1_1") (pintype "unspecified"))
      (node (ref "TB5") (pin "2") (pinfunction "AO1_2") (pintype "unspecified"))
    )
    (net (code "31") (name "Net-(P10-Pad1)") (class "Default")
      (node (ref "P10") (pin "1") (pinfunction "1_1") (pintype "unspecified"))
      (node (ref "TB5") (pin "11") (pinfunction "BO1_11") (pintype "unspecified"))
      (node (ref "TB5") (pin "12") (pinfunction "BO1_12") (pintype "unspecified"))
    )
    (net (code "32") (name "Net-(P10-Pad2)") (class "Default")
      (node (ref "P10") (pin "2") (pinfunction "2_2") (pintype "unspecified"))
      (node (ref "TB5") (pin "7") (pinfunction "BO2_7") (pintype "unspecified"))
      (node (ref "TB5") (pin "8") (pinfunction "BO2_8") (pintype "unspecified"))
    )
    (net (code "33") (name "Net-(P11-Pad1)") (class "Default")
      (node (ref "P11") (pin "1") (pinfunction "1_1") (pintype "unspecified"))
      (node (ref "TB6") (pin "5") (pinfunction "AO2_5") (pintype "unspecified"))
      (node (ref "TB6") (pin "6") (pinfunction "AO2_6") (pintype "unspecified"))
    )
    (net (code "34") (name "Net-(P11-Pad2)") (class "Default")
      (node (ref "P11") (pin "2") (pinfunction "2_2") (pintype "unspecified"))
      (node (ref "TB6") (pin "1") (pinfunction "AO1_1") (pintype "unspecified"))
      (node (ref "TB6") (pin "2") (pinfunction "AO1_2") (pintype "unspecified"))
    )
    (net (code "35") (name "Net-(P12-Pad1)") (class "Default")
      (node (ref "P12") (pin "1") (pinfunction "1_1") (pintype "unspecified"))
      (node (ref "TB6") (pin "11") (pinfunction "BO1_11") (pintype "unspecified"))
      (node (ref "TB6") (pin "12") (pinfunction "BO1_12") (pintype "unspecified"))
    )
    (net (code "36") (name "Net-(P12-Pad2)") (class "Default")
      (node (ref "P12") (pin "2") (pinfunction "2_2") (pintype "unspecified"))
      (node (ref "TB6") (pin "7") (pinfunction "BO2_7") (pintype "unspecified"))
      (node (ref "TB6") (pin "8") (pinfunction "BO2_8") (pintype "unspecified"))
    )
    (net (code "37") (name "Net-(P13-Pad1)") (class "Default")
      (node (ref "P13") (pin "1") (pinfunction "1_1") (pintype "unspecified"))
      (node (ref "TB7") (pin "5") (pinfunction "AO2_5") (pintype "unspecified"))
      (node (ref "TB7") (pin "6") (pinfunction "AO2_6") (pintype "unspecified"))
    )
    (net (code "38") (name "Net-(P13-Pad2)") (class "Default")
      (node (ref "P13") (pin "2") (pinfunction "2_2") (pintype "unspecified"))
      (node (ref "TB7") (pin "1") (pinfunction "AO1_1") (pintype "unspecified"))
      (node (ref "TB7") (pin "2") (pinfunction "AO1_2") (pintype "unspecified"))
    )
    (net (code "39") (name "Net-(P14-Pad1)") (class "Default")
      (node (ref "P14") (pin "1") (pinfunction "1_1") (pintype "unspecified"))
      (node (ref "TB7") (pin "11") (pinfunction "BO1_11") (pintype "unspecified"))
      (node (ref "TB7") (pin "12") (pinfunction "BO1_12") (pintype "unspecified"))
    )
    (net (code "40") (name "Net-(P14-Pad2)") (class "Default")
      (node (ref "P14") (pin "2") (pinfunction "2_2") (pintype "unspecified"))
      (node (ref "TB7") (pin "7") (pinfunction "BO2_7") (pintype "unspecified"))
      (node (ref "TB7") (pin "8") (pinfunction "BO2_8") (pintype "unspecified"))
    )
    (net (code "41") (name "Net-(P15-Pad1)") (class "Default")
      (node (ref "P15") (pin "1") (pinfunction "1_1") (pintype "unspecified"))
      (node (ref "TB8") (pin "5") (pinfunction "AO2_5") (pintype "unspecified"))
      (node (ref "TB8") (pin "6") (pinfunction "AO2_6") (pintype "unspecified"))
    )
    (net (code "42") (name "Net-(P15-Pad2)") (class "Default")
      (node (ref "P15") (pin "2") (pinfunction "2_2") (pintype "unspecified"))
      (node (ref "TB8") (pin "1") (pinfunction "AO1_1") (pintype "unspecified"))
      (node (ref "TB8") (pin "2") (pinfunction "AO1_2") (pintype "unspecified"))
    )
    (net (code "43") (name "Net-(P16-Pad1)") (class "Default")
      (node (ref "P16") (pin "1") (pinfunction "1_1") (pintype "unspecified"))
      (node (ref "TB8") (pin "11") (pinfunction "BO1_11") (pintype "unspecified"))
      (node (ref "TB8") (pin "12") (pinfunction "BO1_12") (pintype "unspecified"))
    )
    (net (code "44") (name "Net-(P16-Pad2)") (class "Default")
      (node (ref "P16") (pin "2") (pinfunction "2_2") (pintype "unspecified"))
      (node (ref "TB8") (pin "7") (pinfunction "BO2_7") (pintype "unspecified"))
      (node (ref "TB8") (pin "8") (pinfunction "BO2_8") (pintype "unspecified"))
    )
    (net (code "45") (name "P20{slash}1") (class "Default")
      (node (ref "MCP20") (pin "21") (pinfunction "GPA0_21") (pintype "unspecified"))
      (node (ref "TB1") (pin "23") (pinfunction "PWMA_23") (pintype "unspecified"))
    )
    (net (code "46") (name "P20{slash}2") (class "Default")
      (node (ref "MCP20") (pin "22") (pinfunction "GPA1_22") (pintype "unspecified"))
      (node (ref "TB1") (pin "15") (pinfunction "PWMB_15") (pintype "unspecified"))
    )
    (net (code "47") (name "P20{slash}3") (class "Default")
      (node (ref "MCP20") (pin "23") (pinfunction "GPA2_23") (pintype "unspecified"))
      (node (ref "TB2") (pin "23") (pinfunction "PWMA_23") (pintype "unspecified"))
    )
    (net (code "48") (name "P20{slash}4") (class "Default")
      (node (ref "MCP20") (pin "24") (pinfunction "GPA3_24") (pintype "unspecified"))
      (node (ref "TB2") (pin "15") (pinfunction "PWMB_15") (pintype "unspecified"))
    )
    (net (code "49") (name "P20{slash}5") (class "Default")
      (node (ref "MCP20") (pin "25") (pinfunction "GPA4_25") (pintype "unspecified"))
      (node (ref "TB3") (pin "23") (pinfunction "PWMA_23") (pintype "unspecified"))
    )
    (net (code "50") (name "P20{slash}6") (class "Default")
      (node (ref "MCP20") (pin "26") (pinfunction "GPA5_26") (pintype "unspecified"))
      (node (ref "TB3") (pin "15") (pinfunction "PWMB_15") (pintype "unspecified"))
    )
    (net (code "51") (name "P20{slash}7") (class "Default")
      (node (ref "MCP20") (pin "27") (pinfunction "GPA6_27") (pintype "unspecified"))
      (node (ref "TB4") (pin "23") (pinfunction "PWMA_23") (pintype "unspecified"))
    )
    (net (code "52") (name "P20{slash}8") (class "Default")
      (node (ref "MCP20") (pin "28") (pinfunction "GPA7_28") (pintype "unspecified"))
      (node (ref "TB4") (pin "15") (pinfunction "PWMB_15") (pintype "unspecified"))
    )
    (net (code "53") (name "P20{slash}9") (class "Default")
      (node (ref "MCP20") (pin "1") (pinfunction "GPB0_1") (pintype "unspecified"))
      (node (ref "TB5") (pin "23") (pinfunction "PWMA_23") (pintype "unspecified"))
    )
    (net (code "54") (name "P20{slash}10") (class "Default")
      (node (ref "MCP20") (pin "2") (pinfunction "GPB1_2") (pintype "unspecified"))
      (node (ref "TB5") (pin "15") (pinfunction "PWMB_15") (pintype "unspecified"))
    )
    (net (code "55") (name "P20{slash}11") (class "Default")
      (node (ref "MCP20") (pin "3") (pinfunction "GPB2_3") (pintype "unspecified"))
      (node (ref "TB6") (pin "23") (pinfunction "PWMA_23") (pintype "unspecified"))
    )
    (net (code "56") (name "P20{slash}12") (class "Default")
      (node (ref "MCP20") (pin "4") (pinfunction "GPB3_4") (pintype "unspecified"))
      (node (ref "TB6") (pin "15") (pinfunction "PWMB_15") (pintype "unspecified"))
    )
    (net (code "57") (name "P20{slash}13") (class "Default")
      (node (ref "MCP20") (pin "5") (pinfunction "GPB4_5") (pintype "unspecified"))
      (node (ref "TB7") (pin "23") (pinfunction "PWMA_23") (pintype "unspecified"))
    )
    (net (code "58") (name "P20{slash}14") (class "Default")
      (node (ref "MCP20") (pin "6") (pinfunction "GPB5_6") (pintype "unspecified"))
      (node (ref "TB7") (pin "15") (pinfunction "PWMB_15") (pintype "unspecified"))
    )
    (net (code "59") (name "P20{slash}15") (class "Default")
      (node (ref "MCP20") (pin "7") (pinfunction "GPB6_7") (pintype "unspecified"))
      (node (ref "TB8") (pin "23") (pinfunction "PWMA_23") (pintype "unspecified"))
    )
    (net (code "60") (name "P20{slash}16") (class "Default")
      (node (ref "MCP20") (pin "8") (pinfunction "GPB7_8") (pintype "unspecified"))
      (node (ref "TB8") (pin "15") (pinfunction "PWMB_15") (pintype "unspecified"))
    )
    (net (code "61") (name "STBY1") (class "Default")
      (node (ref "R1") (pin "1") (pinfunction "1_1") (pintype "input"))
      (node (ref "TB1") (pin "19") (pinfunction "STBY_19") (pintype "unspecified"))
      (node (ref "TB2") (pin "19") (pinfunction "STBY_19") (pintype "unspecified"))
    )
    (net (code "62") (name "STBY2") (class "Default")
      (node (ref "R2") (pin "1") (pinfunction "1_1") (pintype "input"))
      (node (ref "TB3") (pin "19") (pinfunction "STBY_19") (pintype "unspecified"))
      (node (ref "TB4") (pin "19") (pinfunction "STBY_19") (pintype "unspecified"))
    )
    (net (code "63") (name "STBY3") (class "Default")
      (node (ref "R3") (pin "1") (pinfunction "1_1") (pintype "input"))
      (node (ref "TB5") (pin "19") (pinfunction "STBY_19") (pintype "unspecified"))
      (node (ref "TB6") (pin "19") (pinfunction "STBY_19") (pintype "unspecified"))
    )
    (net (code "64") (name "STBY4") (class "Default")
      (node (ref "R4") (pin "1") (pinfunction "1_1") (pintype "input"))
      (node (ref "TB7") (pin "19") (pinfunction "STBY_19") (pintype "unspecified"))
      (node (ref "TB8") (pin "19") (pinfunction "STBY_19") (pintype "unspecified"))
    )
    (net (code "65") (name "unconnected-(MCP20-INTA-Pad20)") (class "Default")
      (node (ref "MCP20") (pin "20") (pinfunction "INTA_20") (pintype "unspecified+no_connect"))
    )
    (net (code "66") (name "unconnected-(MCP20-INTB-Pad19)") (class "Default")
      (node (ref "MCP20") (pin "19") (pinfunction "INTB_19") (pintype "unspecified+no_connect"))
    )
    (net (code "67") (name "unconnected-(MCP20-NC-Pad11)") (class "Default")
      (node (ref "MCP20") (pin "11") (pinfunction "NC_11") (pintype "unspecified+no_connect"))
    )
    (net (code "68") (name "unconnected-(MCP20-NC-Pad14)") (class "Default")
      (node (ref "MCP20") (pin "14") (pinfunction "NC_14") (pintype "unspecified+no_connect"))
    )
    (net (code "69") (name "unconnected-(RPI1-DNC-Pad27)") (class "Default")
      (node (ref "RPI1") (pin "27") (pinfunction "DNC_27") (pintype "unspecified+no_connect"))
    )
    (net (code "70") (name "unconnected-(RPI1-DNC-Pad28)") (class "Default")
      (node (ref "RPI1") (pin "28") (pinfunction "DNC_28") (pintype "unspecified+no_connect"))
    )
    (net (code "71") (name "unconnected-(RPI1-GPIO4-Pad7)") (class "Default")
      (node (ref "RPI1") (pin "7") (pinfunction "GPIO4_7") (pintype "unspecified+no_connect"))
    )
    (net (code "72") (name "unconnected-(RPI1-GPIO5-Pad29)") (class "Default")
      (node (ref "RPI1") (pin "29") (pinfunction "GPIO5_29") (pintype "unspecified+no_connect"))
    )
    (net (code "73") (name "unconnected-(RPI1-GPIO6-Pad31)") (class "Default")
      (node (ref "RPI1") (pin "31") (pinfunction "GPIO6_31") (pintype "unspecified+no_connect"))
    )
    (net (code "74") (name "unconnected-(RPI1-GPIO7-Pad26)") (class "Default")
      (node (ref "RPI1") (pin "26") (pinfunction "GPIO7_26") (pintype "unspecified+no_connect"))
    )
    (net (code "75") (name "unconnected-(RPI1-GPIO8-Pad24)") (class "Default")
      (node (ref "RPI1") (pin "24") (pinfunction "GPIO8_24") (pintype "unspecified+no_connect"))
    )
    (net (code "76") (name "unconnected-(RPI1-GPIO9-Pad21)") (class "Default")
      (node (ref "RPI1") (pin "21") (pinfunction "GPIO9_21") (pintype "unspecified+no_connect"))
    )
    (net (code "77") (name "unconnected-(RPI1-GPIO10-Pad19)") (class "Default")
      (node (ref "RPI1") (pin "19") (pinfunction "GPIO10_19") (pintype "unspecified+no_connect"))
    )
    (net (code "78") (name "unconnected-(RPI1-GPIO11-Pad23)") (class "Default")
      (node (ref "RPI1") (pin "23") (pinfunction "GPIO11_23") (pintype "unspecified+no_connect"))
    )
    (net (code "79") (name "unconnected-(RPI1-GPIO12-Pad32)") (class "Default")
      (node (ref "RPI1") (pin "32") (pinfunction "GPIO12_32") (pintype "unspecified+no_connect"))
    )
    (net (code "80") (name "unconnected-(RPI1-GPIO13-Pad33)") (class "Default")
      (node (ref "RPI1") (pin "33") (pinfunction "GPIO13_33") (pintype "unspecified+no_connect"))
    )
    (net (code "81") (name "unconnected-(RPI1-GPIO14-Pad8)") (class "Default")
      (node (ref "RPI1") (pin "8") (pinfunction "GPIO14_8") (pintype "unspecified+no_connect"))
    )
    (net (code "82") (name "unconnected-(RPI1-GPIO15-Pad10)") (class "Default")
      (node (ref "RPI1") (pin "10") (pinfunction "GPIO15_10") (pintype "unspecified+no_connect"))
    )
    (net (code "83") (name "unconnected-(RPI1-GPIO16-Pad36)") (class "Default")
      (node (ref "RPI1") (pin "36") (pinfunction "GPIO16_36") (pintype "unspecified+no_connect"))
    )
    (net (code "84") (name "unconnected-(RPI1-GPIO18-Pad12)") (class "Default")
      (node (ref "RPI1") (pin "12") (pinfunction "GPIO18_12") (pintype "unspecified+no_connect"))
    )
    (net (code "85") (name "unconnected-(RPI1-GPIO19-Pad35)") (class "Default")
      (node (ref "RPI1") (pin "35") (pinfunction "GPIO19_35") (pintype "unspecified+no_connect"))
    )
    (net (code "86") (name "unconnected-(RPI1-GPIO20-Pad38)") (class "Default")
      (node (ref "RPI1") (pin "38") (pinfunction "GPIO20_38") (pintype "unspecified+no_connect"))
    )
    (net (code "87") (name "unconnected-(RPI1-GPIO21-Pad40)") (class "Default")
      (node (ref "RPI1") (pin "40") (pinfunction "GPIO21_40") (pintype "unspecified+no_connect"))
    )
    (net (code "88") (name "unconnected-(RPI1-GPIO23-Pad16)") (class "Default")
      (node (ref "RPI1") (pin "16") (pinfunction "GPIO23_16") (pintype "unspecified+no_connect"))
    )
    (net (code "89") (name "unconnected-(RPI1-GPIO24-Pad18)") (class "Default")
      (node (ref "RPI1") (pin "18") (pinfunction "GPIO24_18") (pintype "unspecified+no_connect"))
    )
    (net (code "90") (name "unconnected-(RPI1-GPIO25-Pad22)") (class "Default")
      (node (ref "RPI1") (pin "22") (pinfunction "GPIO25_22") (pintype "unspecified+no_connect"))
    )
    (net (code "91") (name "unconnected-(RPI1-GPIO26-Pad37)") (class "Default")
      (node (ref "RPI1") (pin "37") (pinfunction "GPIO26_37") (pintype "unspecified+no_connect"))
    )
  )
)
